# KeyboardRemapper.net
KiCad netlist of a schematic drawn in EAGLE
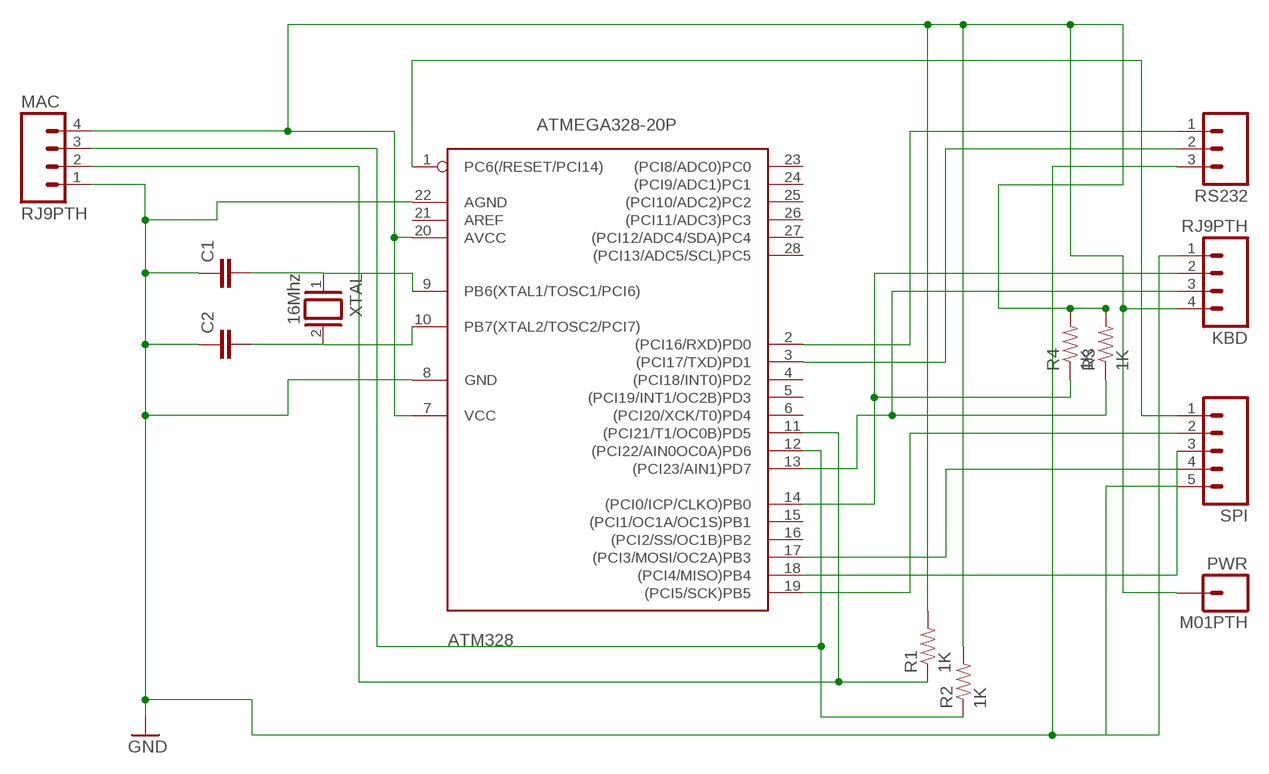
[diagram p0: schematic, sheet 1]

(export (version "E")
  (design (tool "Eeschema 10.0.6"))
  (components
    (comp (ref "ATM328")
      (value "ATMEGA328-20P")
      (footprint "eagle-import:DIL28-3")
      (libsource (lib "eagle-import") (part "ATMEGA328P-20"))
    )
    (comp (ref "C1")
      (value "CAPPTH2")
      (footprint "eagle-import:CAP-PTH-SMALL2")
      (libsource (lib "eagle-import") (part "CAPPTH2"))
    )
    (comp (ref "C2")
      (value "CAPPTH2")
      (footprint "eagle-import:CAP-PTH-SMALL2")
      (libsource (lib "eagle-import") (part "CAPPTH2"))
    )
    (comp (ref "KBD")
      (value "RJ9PTH")
      (footprint "eagle-import:RJ9")
      (libsource (lib "eagle-import") (part "RJ9PTH"))
    )
    (comp (ref "MAC")
      (value "RJ9PTH")
      (footprint "eagle-import:RJ9")
      (libsource (lib "eagle-import") (part "RJ9PTH"))
    )
    (comp (ref "PWR")
      (value "M01PTH")
      (footprint "eagle-import:1X01")
      (libsource (lib "eagle-import") (part "M01PTH"))
    )
    (comp (ref "R1")
      (value "1K")
      (footprint "eagle-import:AXIAL-0.3")
      (libsource (lib "eagle-import") (part "RESISTORPTH1"))
    )
    (comp (ref "R2")
      (value "1K")
      (footprint "eagle-import:AXIAL-0.3")
      (libsource (lib "eagle-import") (part "RESISTORPTH1"))
    )
    (comp (ref "R3")
      (value "1K")
      (footprint "eagle-import:AXIAL-0.3")
      (libsource (lib "eagle-import") (part "RESISTORPTH1"))
    )
    (comp (ref "R4")
      (value "1K")
      (footprint "eagle-import:AXIAL-0.3")
      (libsource (lib "eagle-import") (part "RESISTORPTH1"))
    )
    (comp (ref "RS232")
      (value "M03PTH")
      (footprint "eagle-import:1X03")
      (libsource (lib "eagle-import") (part "M03PTH"))
    )
    (comp (ref "SPI")
      (value "M05PTH")
      (footprint "eagle-import:1X05")
      (libsource (lib "eagle-import") (part "M05PTH"))
    )
    (comp (ref "XTAL")
      (value "16Mhz")
      (footprint "eagle-import:QS")
      (libsource (lib "eagle-import") (part "XTAL/S"))
    )
  )
  (nets
    (net (code "1") (name "GND") (class "Default")
      (node (ref "ATM328") (pin "22") (pinfunction "AGND_22") (pintype "bidirectional"))
      (node (ref "ATM328") (pin "8") (pinfunction "GND_8") (pintype "bidirectional"))
      (node (ref "C1") (pin "1") (pinfunction "1_1") (pintype "passive"))
      (node (ref "C2") (pin "1") (pinfunction "1_1") (pintype "passive"))
      (node (ref "KBD") (pin "1") (pinfunction "1_1") (pintype "passive"))
      (node (ref "MAC") (pin "1") (pinfunction "1_1") (pintype "passive"))
      (node (ref "RS232") (pin "3") (pinfunction "3_3") (pintype "passive"))
      (node (ref "SPI") (pin "5") (pinfunction "5_5") (pintype "passive"))
    )
    (net (code "2") (name "Net-(ATM328-(PCI0{slash}ICP{slash}CLKO)PB0)") (class "Default")
      (node (ref "ATM328") (pin "14") (pinfunction "(PCI0/ICP/CLKO)PB0_14") (pintype "bidirectional"))
      (node (ref "KBD") (pin "2") (pinfunction "2_2") (pintype "passive"))
      (node (ref "R4") (pin "P$1") (pinfunction "1_P$1") (pintype "passive"))
    )
    (net (code "3") (name "Net-(ATM328-(PCI3{slash}MOSI{slash}OC2A)PB3)") (class "Default")
      (node (ref "ATM328") (pin "17") (pinfunction "(PCI3/MOSI/OC2A)PB3_17") (pintype "bidirectional"))
      (node (ref "SPI") (pin "4") (pinfunction "4_4") (pintype "passive"))
    )
    (net (code "4") (name "Net-(ATM328-(PCI4{slash}MISO)PB4)") (class "Default")
      (node (ref "ATM328") (pin "18") (pinfunction "(PCI4/MISO)PB4_18") (pintype "bidirectional"))
      (node (ref "SPI") (pin "3") (pinfunction "3_3") (pintype "passive"))
    )
    (net (code "5") (name "Net-(ATM328-(PCI5{slash}SCK)PB5)") (class "Default")
      (node (ref "ATM328") (pin "19") (pinfunction "(PCI5/SCK)PB5_19") (pintype "bidirectional"))
      (node (ref "SPI") (pin "2") (pinfunction "2_2") (pintype "passive"))
    )
    (net (code "6") (name "Net-(ATM328-(PCI16{slash}RXD)PD0)") (class "Default")
      (node (ref "ATM328") (pin "2") (pinfunction "(PCI16/RXD)PD0_2") (pintype "bidirectional"))
      (node (ref "RS232") (pin "1") (pinfunction "1_1") (pintype "passive"))
    )
    (net (code "7") (name "Net-(ATM328-(PCI17{slash}TXD)PD1)") (class "Default")
      (node (ref "ATM328") (pin "3") (pinfunction "(PCI17/TXD)PD1_3") (pintype "bidirectional"))
      (node (ref "RS232") (pin "2") (pinfunction "2_2") (pintype "passive"))
    )
    (net (code "8") (name "Net-(ATM328-(PCI21{slash}T1{slash}OC0B)PD5)") (class "Default")
      (node (ref "ATM328") (pin "11") (pinfunction "(PCI21/T1/OC0B)PD5_11") (pintype "bidirectional"))
      (node (ref "MAC") (pin "2") (pinfunction "2_2") (pintype "passive"))
      (node (ref "R1") (pin "P$1") (pinfunction "1_P$1") (pintype "passive"))
    )
    (net (code "9") (name "Net-(ATM328-(PCI22{slash}AIN0OC0A)PD6)") (class "Default")
      (node (ref "ATM328") (pin "12") (pinfunction "(PCI22/AIN0OC0A)PD6_12") (pintype "bidirectional"))
      (node (ref "MAC") (pin "3") (pinfunction "3_3") (pintype "passive"))
      (node (ref "R2") (pin "P$1") (pinfunction "1_P$1") (pintype "passive"))
    )
    (net (code "10") (name "Net-(ATM328-(PCI23{slash}AIN1)PD7)") (class "Default")
      (node (ref "ATM328") (pin "13") (pinfunction "(PCI23/AIN1)PD7_13") (pintype "bidirectional"))
      (node (ref "KBD") (pin "3") (pinfunction "3_3") (pintype "passive"))
      (node (ref "R3") (pin "P$1") (pinfunction "1_P$1") (pintype "passive"))
    )
    (net (code "11") (name "Net-(ATM328-AVCC)") (class "Default")
      (node (ref "ATM328") (pin "20") (pinfunction "AVCC_20") (pintype "bidirectional"))
      (node (ref "ATM328") (pin "7") (pinfunction "VCC_7") (pintype "bidirectional"))
      (node (ref "KBD") (pin "4") (pinfunction "4_4") (pintype "passive"))
      (node (ref "MAC") (pin "4") (pinfunction "4_4") (pintype "passive"))
      (node (ref "PWR") (pin "1") (pinfunction "1_1") (pintype "passive"))
      (node (ref "R1") (pin "P$2") (pinfunction "2_P$2") (pintype "passive"))
      (node (ref "R2") (pin "P$2") (pinfunction "2_P$2") (pintype "passive"))
      (node (ref "R3") (pin "P$2") (pinfunction "2_P$2") (pintype "passive"))
      (node (ref "R4") (pin "P$2") (pinfunction "2_P$2") (pintype "passive"))
    )
    (net (code "12") (name "Net-(ATM328-PB6(XTAL1{slash}TOSC1{slash}PCI6))") (class "Default")
      (node (ref "ATM328") (pin "9") (pinfunction "PB6(XTAL1/TOSC1/PCI6)_9") (pintype "bidirectional"))
      (node (ref "C1") (pin "2") (pinfunction "2_2") (pintype "passive"))
      (node (ref "XTAL") (pin "1") (pinfunction "1_1") (pintype "passive"))
    )
    (net (code "13") (name "Net-(ATM328-PB7(XTAL2{slash}TOSC2{slash}PCI7))") (class "Default")
      (node (ref "ATM328") (pin "10") (pinfunction "PB7(XTAL2/TOSC2/PCI7)_10") (pintype "bidirectional"))
      (node (ref "C2") (pin "2") (pinfunction "2_2") (pintype "passive"))
      (node (ref "XTAL") (pin "2") (pinfunction "2_2") (pintype "passive"))
    )
    (net (code "14") (name "Net-(ATM328-PC6({slash}RESET{slash}PCI14))") (class "Default")
      (node (ref "ATM328") (pin "1") (pinfunction "PC6(/RESET/PCI14)_1") (pintype "bidirectional"))
      (node (ref "SPI") (pin "1") (pinfunction "1_1") (pintype "passive"))
    )
    (net (code "15") (name "unconnected-(ATM328-(PCI1{slash}OC1A{slash}OC1S)PB1-Pad15)") (class "Default")
      (node (ref "ATM328") (pin "15") (pinfunction "(PCI1/OC1A/OC1S)PB1_15") (pintype "bidirectional"))
    )
    (net (code "16") (name "unconnected-(ATM328-(PCI2{slash}SS{slash}OC1B)PB2-Pad16)") (class "Default")
      (node (ref "ATM328") (pin "16") (pinfunction "(PCI2/SS/OC1B)PB2_16") (pintype "bidirectional"))
    )
    (net (code "17") (name "unconnected-(ATM328-(PCI8{slash}ADC0)PC0-Pad23)") (class "Default")
      (node (ref "ATM328") (pin "23") (pinfunction "(PCI8/ADC0)PC0_23") (pintype "bidirectional"))
    )
    (net (code "18") (name "unconnected-(ATM328-(PCI9{slash}ADC1)PC1-Pad24)") (class "Default")
      (node (ref "ATM328") (pin "24") (pinfunction "(PCI9/ADC1)PC1_24") (pintype "bidirectional"))
    )
    (net (code "19") (name "unconnected-(ATM328-(PCI10{slash}ADC2)PC2-Pad25)") (class "Default")
      (node (ref "ATM328") (pin "25") (pinfunction "(PCI10/ADC2)PC2_25") (pintype "bidirectional"))
    )
    (net (code "20") (name "unconnected-(ATM328-(PCI11{slash}ADC3)PC3-Pad26)") (class "Default")
      (node (ref "ATM328") (pin "26") (pinfunction "(PCI11/ADC3)PC3_26") (pintype "bidirectional"))
    )
    (net (code "21") (name "unconnected-(ATM328-(PCI12{slash}ADC4{slash}SDA)PC4-Pad27)") (class "Default")
      (node (ref "ATM328") (pin "27") (pinfunction "(PCI12/ADC4/SDA)PC4_27") (pintype "bidirectional"))
    )
    (net (code "22") (name "unconnected-(ATM328-(PCI13{slash}ADC5{slash}SCL)PC5-Pad28)") (class "Default")
      (node (ref "ATM328") (pin "28") (pinfunction "(PCI13/ADC5/SCL)PC5_28") (pintype "bidirectional"))
    )
    (net (code "23") (name "unconnected-(ATM328-(PCI18{slash}INT0)PD2-Pad4)") (class "Default")
      (node (ref "ATM328") (pin "4") (pinfunction "(PCI18/INT0)PD2_4") (pintype "bidirectional"))
    )
    (net (code "24") (name "unconnected-(ATM328-(PCI19{slash}INT1{slash}OC2B)PD3-Pad5)") (class "Default")
      (node (ref "ATM328") (pin "5") (pinfunction "(PCI19/INT1/OC2B)PD3_5") (pintype "bidirectional"))
    )
    (net (code "25") (name "unconnected-(ATM328-(PCI20{slash}XCK{slash}T0)PD4-Pad6)") (class "Default")
      (node (ref "ATM328") (pin "6") (pinfunction "(PCI20/XCK/T0)PD4_6") (pintype "bidirectional"))
    )
    (net (code "26") (name "unconnected-(ATM328-AREF-Pad21)") (class "Default")
      (node (ref "ATM328") (pin "21") (pinfunction "AREF_21") (pintype "bidirectional"))
    )
  )
)
